# SCH1.net
KiCad netlist of a schematic drawn in Altium Designer
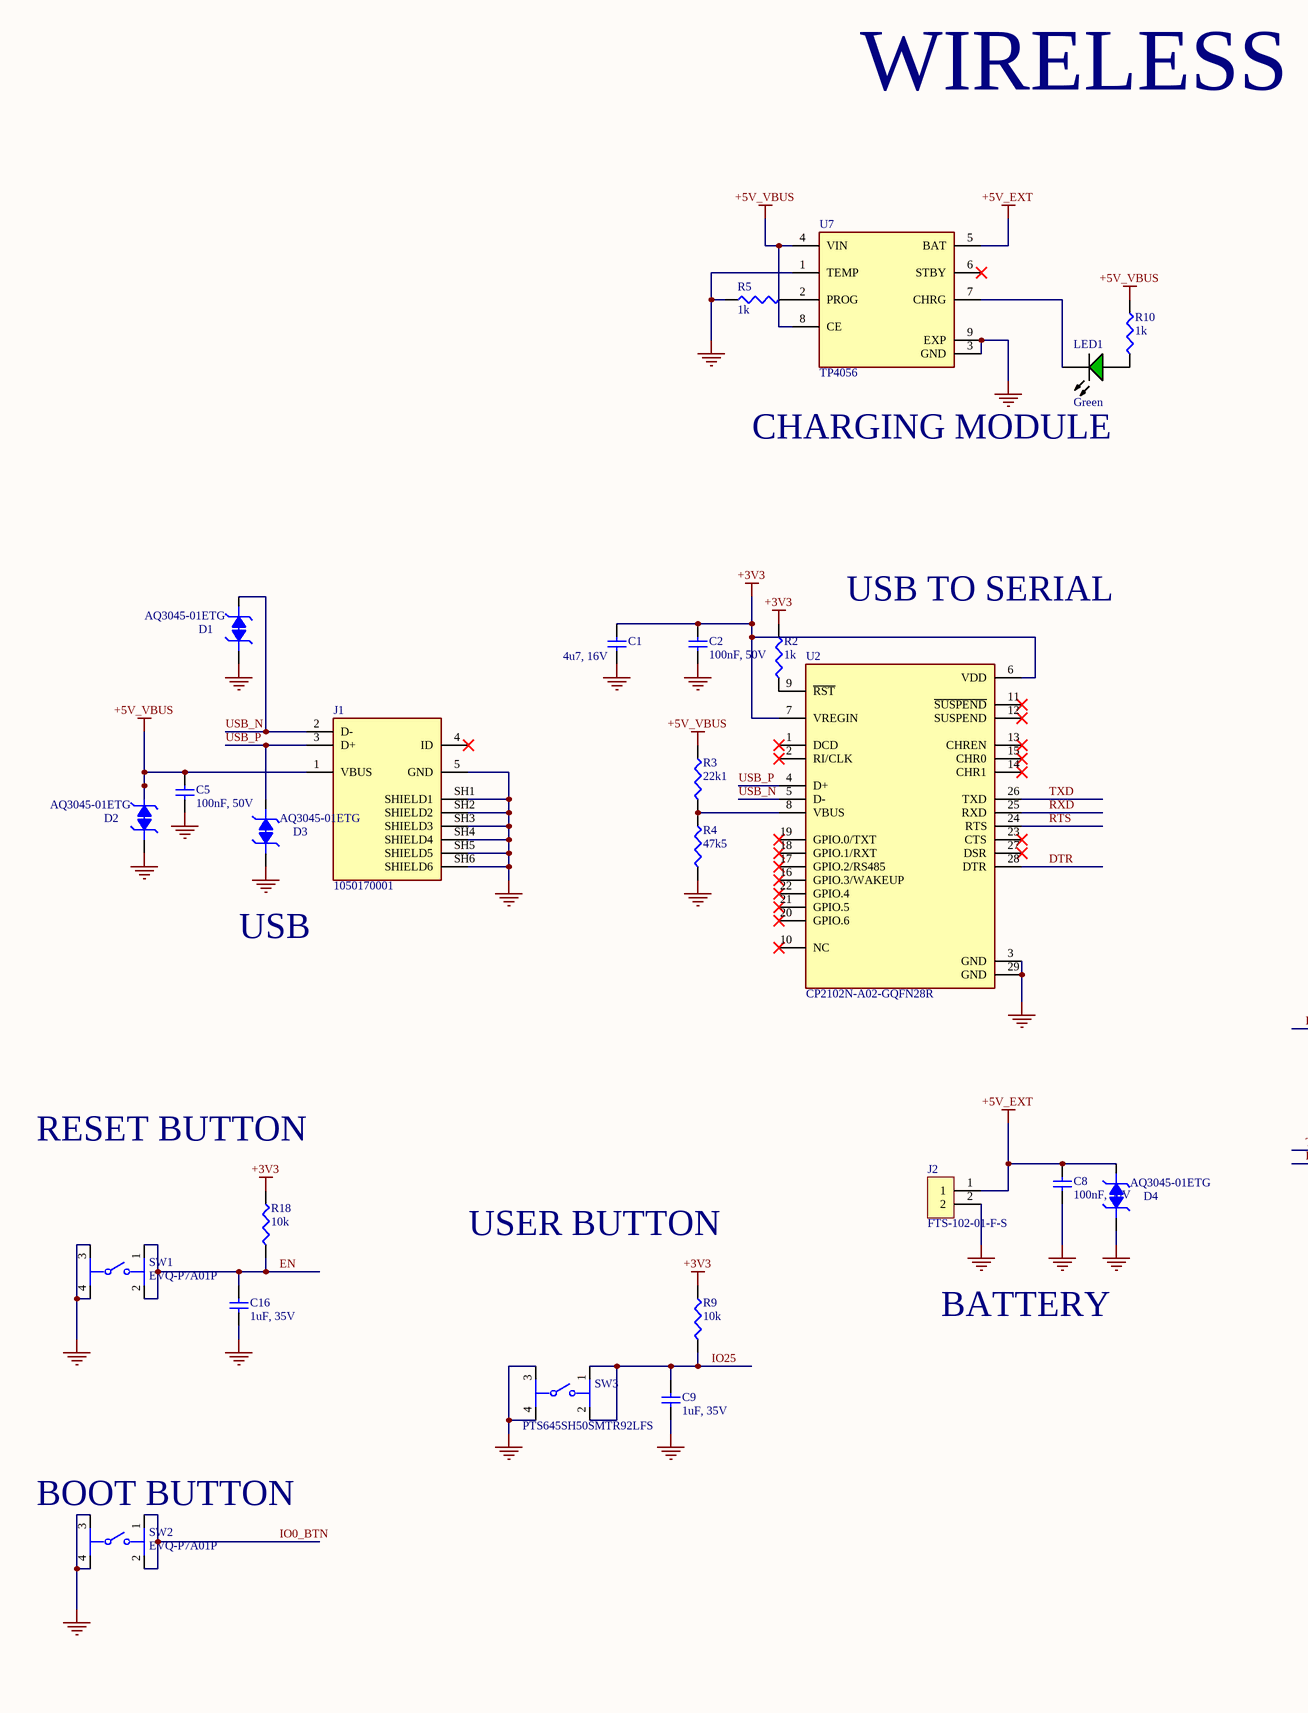
[diagram p0: SCH1.SchDoc, left]
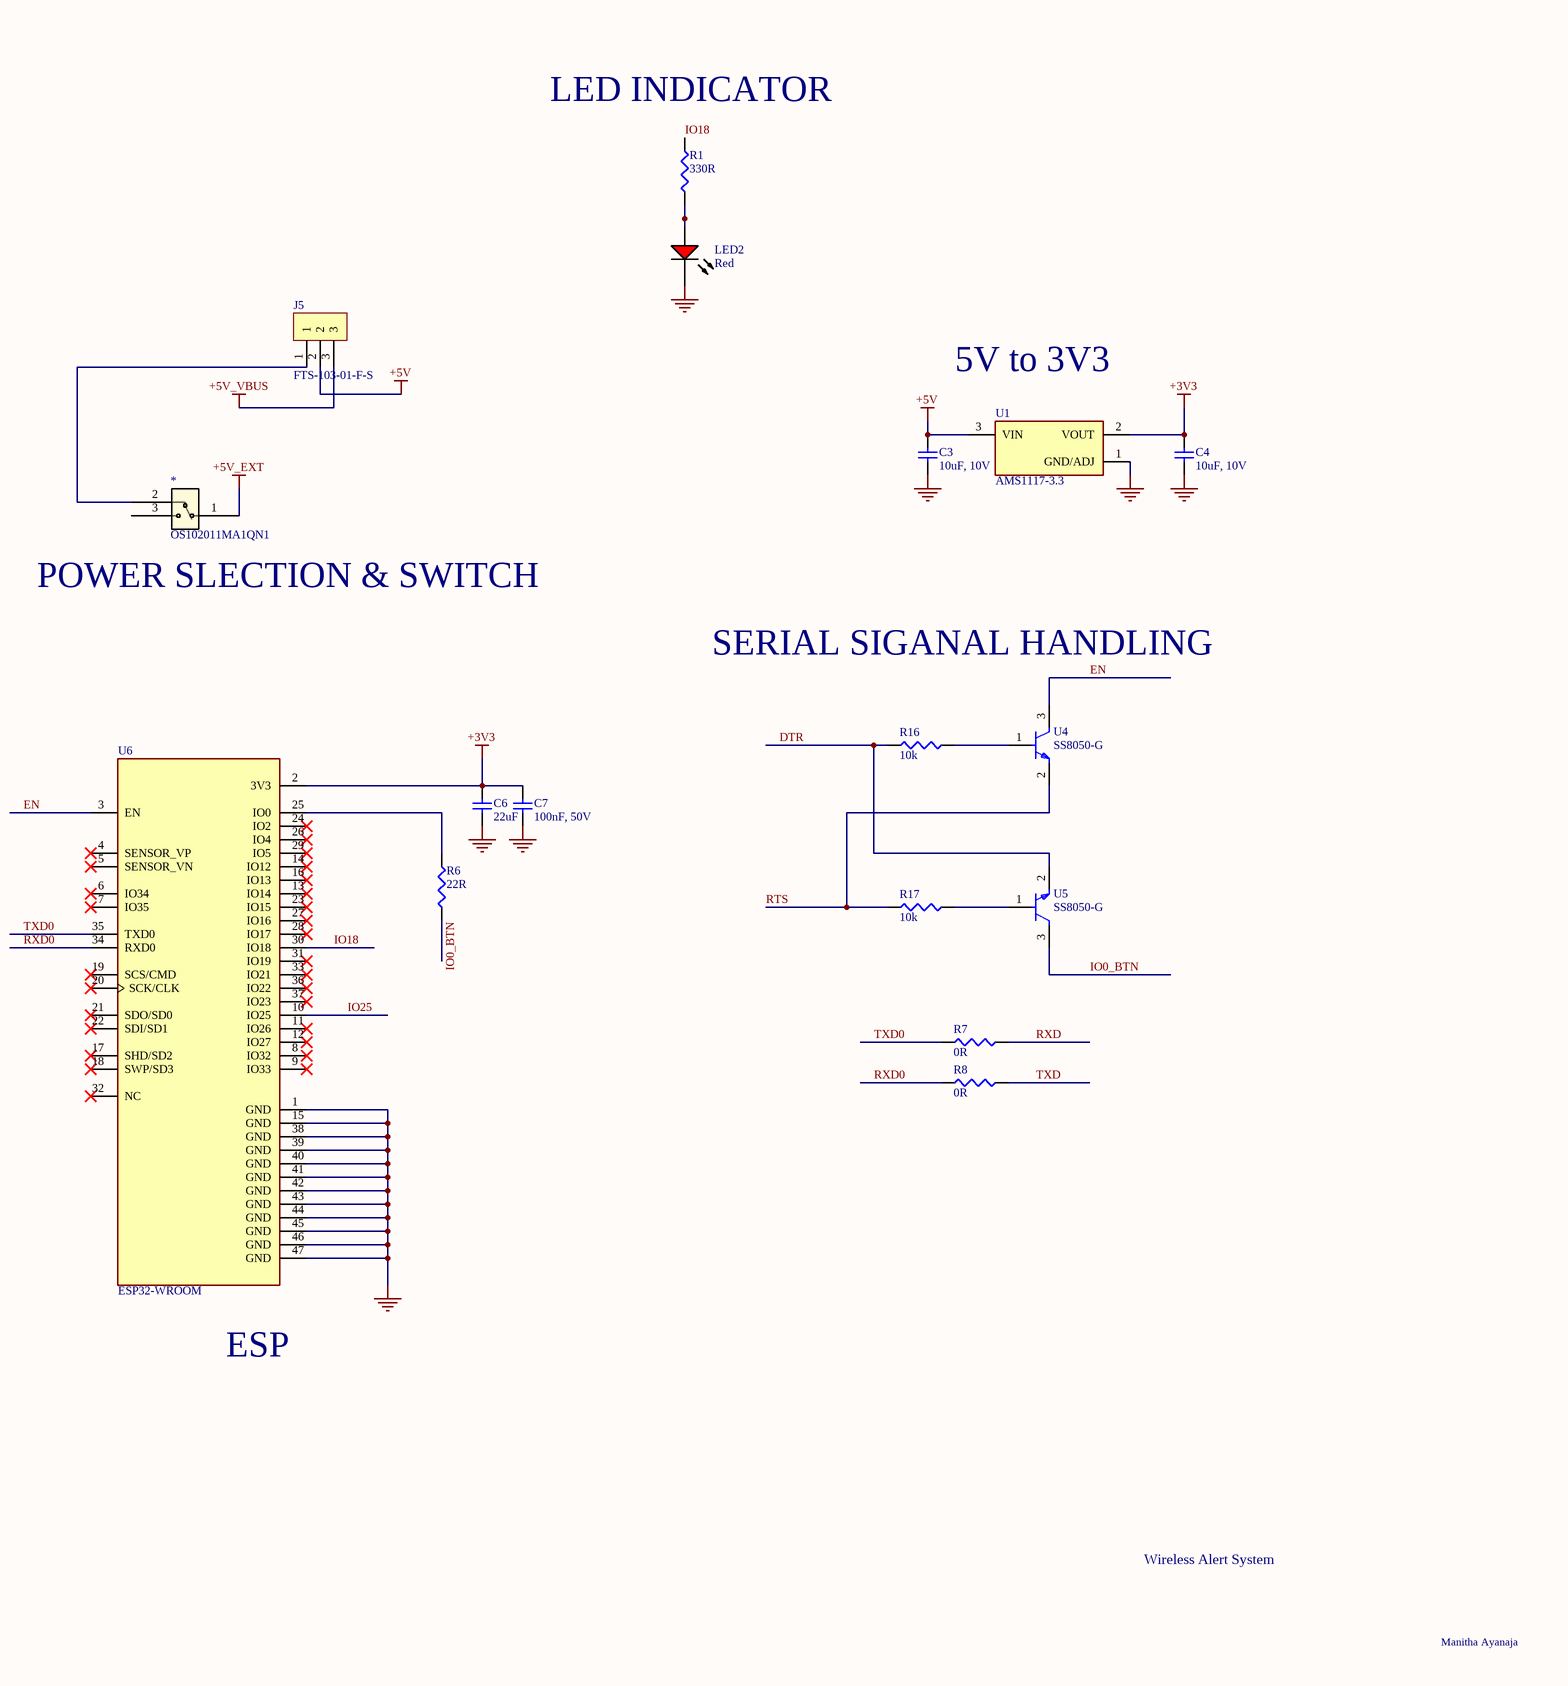
[diagram p1: SCH1.SchDoc, right]

(export (version "E")
  (design (tool "Eeschema 10.0.6"))
  (components
    (comp (ref "*")
      (value "OS102011MA1QN1")
      (footprint "OS102011MA1QN1_CNK")
      (description "Slide Switch, SPDT, Latched, 0.1A, 12VDC, Solder Terminal, Through Hole-right Angle")
      (fields (field (name "MANUFACTURER") "ITT C&K"))
      (libsource (lib "Schlib") (part "OS102011MA1QN1"))
    )
    (comp (ref "C1")
      (value "4u7, 16V")
      (footprint "CAPC1005X70N")
      (description "CAP CER 4.7UF 16V X5R 0402")
      (fields
        (field (name "MANUFACTURER") "Samsung")
        (field (name "MANUFACTURER PART NUMBER") "CL05A475MO5NUNC")
      )
      (libsource (lib "Schlib") (part "CL05A475MO5NUNC"))
    )
    (comp (ref "C2")
      (value "100nF, 50V")
      (footprint "CAPC1005X70N")
      (description "CAP CER 0.1UF 50V X7R 0402")
      (fields
        (field (name "MANUFACTURER") "Samsung")
        (field (name "MANUFACTURER PART NUMBER") "CL05B104KB54PNC")
      )
      (libsource (lib "Schlib") (part "CL05B104KB54PNC"))
    )
    (comp (ref "C3")
      (value "10uF, 10V")
      (footprint "CAPC1005X70N")
      (description "CAP CER 10UF 10V X5R 0402")
      (fields
        (field (name "MANUFACTURER") "Samsung")
        (field (name "MANUFACTURER PART NUMBER") "CL05A106MP8NUB8")
      )
      (libsource (lib "Schlib") (part "CL05A106MP8NUB8"))
    )
    (comp (ref "C4")
      (value "10uF, 10V")
      (footprint "CAPC1005X70N")
      (description "CAP CER 10UF 10V X5R 0402")
      (fields
        (field (name "MANUFACTURER") "Samsung")
        (field (name "MANUFACTURER PART NUMBER") "CL05A106MP8NUB8")
      )
      (libsource (lib "Schlib") (part "CL05A106MP8NUB8"))
    )
    (comp (ref "C5")
      (value "100nF, 50V")
      (footprint "CAPC1005X70N")
      (description "CAP CER 0.1UF 50V X7R 0402")
      (fields
        (field (name "MANUFACTURER") "Samsung")
        (field (name "MANUFACTURER PART NUMBER") "CL05B104KB54PNC")
      )
      (libsource (lib "Schlib") (part "CL05B104KB54PNC"))
    )
    (comp (ref "C6")
      (value "22uF")
      (footprint "CAPC1005X70N")
      (description "22 µF ±20% 6.3V Ceramic Capacitor X5R 0402 (1005 Metric)")
      (fields
        (field (name "MANUFACTURER") "Samsung")
        (field (name "MANUFACTURER PART NUMBER") "CL05A226MQ5QUNC")
      )
      (libsource (lib "Schlib") (part "CL05A226MQ5QUNC"))
    )
    (comp (ref "C7")
      (value "100nF, 50V")
      (footprint "CAPC1005X70N")
      (description "CAP CER 0.1UF 50V X7R 0402")
      (fields
        (field (name "MANUFACTURER") "Samsung")
        (field (name "MANUFACTURER PART NUMBER") "CL05B104KB54PNC")
      )
      (libsource (lib "Schlib") (part "CL05B104KB54PNC"))
    )
    (comp (ref "C8")
      (value "100nF, 50V")
      (footprint "CAPC1005X70N")
      (description "CAP CER 0.1UF 50V X7R 0402")
      (fields
        (field (name "MANUFACTURER") "Samsung")
        (field (name "MANUFACTURER PART NUMBER") "CL05B104KB54PNC")
      )
      (libsource (lib "Schlib") (part "CL05B104KB54PNC"))
    )
    (comp (ref "C9")
      (value "1uF, 35V")
      (footprint "CAPC1005X70N")
      (description "1 µF ±10% 35V Ceramic Capacitor X5R 0402 (1005 Metric)")
      (fields
        (field (name "MANUFACTURER") "Samsung")
        (field (name "MANUFACTURER PART NUMBER") "CL05A105KL5NRNC")
      )
      (libsource (lib "Schlib") (part "CL05A105KL5NRNC"))
    )
    (comp (ref "C16")
      (value "1uF, 35V")
      (footprint "CAPC1005X70N")
      (description "1 µF ±10% 35V Ceramic Capacitor X5R 0402 (1005 Metric)")
      (fields
        (field (name "MANUFACTURER") "Samsung")
        (field (name "MANUFACTURER PART NUMBER") "CL05A105KL5NRNC")
      )
      (libsource (lib "Schlib") (part "CL05A105KL5NRNC"))
    )
    (comp (ref "D1")
      (value "AQ3045-01ETG")
      (footprint "SOD882")
      (description "TVS DIODE 5.3VWM 12VC SOD882")
      (fields (field (name "MANUFACTURER") "Littelfuse") (field (name "LCSC PART NUMBER") "C3710326"))
      (libsource (lib "Schlib") (part "AQ3045-01ETG"))
    )
    (comp (ref "D2")
      (value "AQ3045-01ETG")
      (footprint "SOD882")
      (description "TVS DIODE 5.3VWM 12VC SOD882")
      (fields (field (name "MANUFACTURER") "Littelfuse") (field (name "LCSC PART NUMBER") "C3710326"))
      (libsource (lib "Schlib") (part "AQ3045-01ETG"))
    )
    (comp (ref "D3")
      (value "AQ3045-01ETG")
      (footprint "SOD882")
      (description "TVS DIODE 5.3VWM 12VC SOD882")
      (fields (field (name "MANUFACTURER") "Littelfuse") (field (name "LCSC PART NUMBER") "C3710326"))
      (libsource (lib "Schlib") (part "AQ3045-01ETG"))
    )
    (comp (ref "D4")
      (value "AQ3045-01ETG")
      (footprint "SOD882")
      (description "TVS DIODE 5.3VWM 12VC SOD882")
      (fields (field (name "MANUFACTURER") "Littelfuse") (field (name "LCSC PART NUMBER") "C3710326"))
      (libsource (lib "Schlib") (part "AQ3045-01ETG"))
    )
    (comp (ref "J1")
      (value "1050170001")
      (footprint "MOLEX_1050170001")
      (description "CONN RCPT USB2.0 MICRO B SMD R/A")
      (fields (field (name "MANUFACTURER") "Molex") (field (name "LCSC PART NUMBER") "C136000"))
      (libsource (lib "Schlib") (part "1050170001"))
    )
    (comp (ref "J2")
      (value "FTS-102-01-F-S")
      (footprint "HDR_1X2_1.27MM")
      (description "Connector Header Through Hole 2 position 0.050\" (1.27mm)")
      (fields (field (name "MANUFACTURER") "Samtec") (field (name "LCSC PART NUMBER") "C6045317"))
      (libsource (lib "Schlib") (part "FTS-102-01-F-S"))
    )
    (comp (ref "J5")
      (value "FTS-103-01-F-S")
      (footprint "HDR_1X3_1.27MM")
      (description "CONN HEADER VERT 3POS 1.27MM")
      (fields (field (name "MANUFACTURER") "Samtec") (field (name "LCSC PART NUMBER") "C3333578"))
      (libsource (lib "Schlib") (part "FTS-103-01-F-S"))
    )
    (comp (ref "LED1")
      (value "Green")
      (footprint "LEDC2012X120N")
      (description "Green LED Indication - Discrete 2V 0805 (2012 Metric)")
      (fields (field (name "LCSC PART NUMBER") "C6296788"))
      (libsource (lib "Schlib") (part "CMP-1724-00001-1"))
    )
    (comp (ref "LED2")
      (value "Red")
      (footprint "LEDC2012X120N")
      (description "Red LED Indication - Discrete 2V 0805 (2012 Metric)")
      (fields
        (field (name "MANUFACTURER") "Lumex")
        (field (name "MANUFACTURER PART NUMBER") "SML-LXT0805IW-TR")
      )
      (libsource (lib "Schlib") (part "SML-LXT0805IW-TR"))
    )
    (comp (ref "R1")
      (value "330R")
      (footprint "RESC1005X40N")
      (description "330 Ohms ±1% 0.063W, 1/16W Chip Resistor 0402 (1005 Metric) Moisture Resistant Thick Film")
      (fields
        (field (name "MANUFACTURER") "Yageo")
        (field (name "MANUFACTURER PART NUMBER") "RC0402FR-07330RL")
      )
      (libsource (lib "Schlib") (part "RC0402FR-07330RL"))
    )
    (comp (ref "R2")
      (value "1k")
      (footprint "RESC1005X40N")
      (description "1 kOhms ±1% 0.063W, 1/16W Chip Resistor 0402 (1005 Metric) Moisture Resistant Thick Film")
      (fields
        (field (name "MANUFACTURER") "Yageo")
        (field (name "MANUFACTURER PART NUMBER") "RC0402FR-071KL")
      )
      (libsource (lib "Schlib") (part "RC0402FR-071KL"))
    )
    (comp (ref "R3")
      (value "22k1")
      (footprint "RESC1005X40N")
      (description "22.1 kOhms ±1% 0.063W, 1/16W Chip Resistor 0402 (1005 Metric) Moisture Resistant Thick Film")
      (fields
        (field (name "MANUFACTURER") "Yageo")
        (field (name "MANUFACTURER PART NUMBER") "RC0402FR-0722K1L")
      )
      (libsource (lib "Schlib") (part "RC0402FR-0722K1L"))
    )
    (comp (ref "R4")
      (value "47k5")
      (footprint "RESC1005X40N")
      (description "47.5 kOhms ±1% 0.063W, 1/16W Chip Resistor 0402 (1005 Metric) Moisture Resistant Thick Film")
      (fields
        (field (name "MANUFACTURER") "Yageo")
        (field (name "MANUFACTURER PART NUMBER") "RC0402FR-1047K5L")
      )
      (libsource (lib "Schlib") (part "RC0402FR-1047K5L"))
    )
    (comp (ref "R5")
      (value "1k")
      (footprint "RESC1005X40N")
      (description "1 kOhms ±1% 0.063W, 1/16W Chip Resistor 0402 (1005 Metric) Moisture Resistant Thick Film")
      (fields
        (field (name "MANUFACTURER") "Yageo")
        (field (name "MANUFACTURER PART NUMBER") "RC0402FR-071KL")
      )
      (libsource (lib "Schlib") (part "RC0402FR-071KL"))
    )
    (comp (ref "R6")
      (value "22R")
      (footprint "RESC1005X40N")
      (description "RES 22 OHM 1% 1/16W 0402")
      (fields
        (field (name "MANUFACTURER") "Yageo")
        (field (name "MANUFACTURER PART NUMBER") "RC0402FR-0722RL")
      )
      (libsource (lib "Schlib") (part "RC0402FR-0722RL"))
    )
    (comp (ref "R7")
      (value "0R")
      (footprint "RESC1005X40N")
      (description "RES 0 OHM JUMPER 1/16W 0402")
      (fields
        (field (name "MANUFACTURER") "Yageo")
        (field (name "MANUFACTURER PART NUMBER") "RC0402JR-070RL")
      )
      (libsource (lib "Schlib") (part "RC0402JR-070RL"))
    )
    (comp (ref "R8")
      (value "0R")
      (footprint "RESC1005X40N")
      (description "RES 0 OHM JUMPER 1/16W 0402")
      (fields
        (field (name "MANUFACTURER") "Yageo")
        (field (name "MANUFACTURER PART NUMBER") "RC0402JR-070RL")
      )
      (libsource (lib "Schlib") (part "RC0402JR-070RL"))
    )
    (comp (ref "R9")
      (value "10k")
      (footprint "RESC1005X40N")
      (description "RES SMD 10K OHM 1% 1/16W 0402")
      (fields
        (field (name "MANUFACTURER") "Yageo")
        (field (name "MANUFACTURER PART NUMBER") "AC0402FR-0710KL")
      )
      (libsource (lib "Schlib") (part "AC0402FR-0710KL"))
    )
    (comp (ref "R10")
      (value "1k")
      (footprint "RESC1005X40N")
      (description "1 kOhms ±1% 0.063W, 1/16W Chip Resistor 0402 (1005 Metric) Moisture Resistant Thick Film")
      (fields
        (field (name "MANUFACTURER") "Yageo")
        (field (name "MANUFACTURER PART NUMBER") "RC0402FR-071KL")
      )
      (libsource (lib "Schlib") (part "RC0402FR-071KL"))
    )
    (comp (ref "R16")
      (value "10k")
      (footprint "RESC1005X40N")
      (description "RES SMD 10K OHM 1% 1/16W 0402")
      (fields
        (field (name "MANUFACTURER") "Yageo")
        (field (name "MANUFACTURER PART NUMBER") "AC0402FR-0710KL")
      )
      (libsource (lib "Schlib") (part "AC0402FR-0710KL"))
    )
    (comp (ref "R17")
      (value "10k")
      (footprint "RESC1005X40N")
      (description "RES SMD 10K OHM 1% 1/16W 0402")
      (fields
        (field (name "MANUFACTURER") "Yageo")
        (field (name "MANUFACTURER PART NUMBER") "AC0402FR-0710KL")
      )
      (libsource (lib "Schlib") (part "AC0402FR-0710KL"))
    )
    (comp (ref "R18")
      (value "10k")
      (footprint "RESC1005X40N")
      (description "RES SMD 10K OHM 1% 1/16W 0402")
      (fields
        (field (name "MANUFACTURER") "Yageo")
        (field (name "MANUFACTURER PART NUMBER") "AC0402FR-0710KL")
      )
      (libsource (lib "Schlib") (part "AC0402FR-0710KL"))
    )
    (comp (ref "SW1")
      (value "EVQ-P7A01P")
      (footprint "SW_EVQ-P7A01P")
      (description "Tactile Switch SPST-NO Side Actuated Surface Mount, Right Angle")
      (fields (field (name "MANUFACTURER") "Panasonic") (field (name "LCSC PART NUMBER") "C79167"))
      (libsource (lib "Schlib") (part "EVQ-P7A01P"))
    )
    (comp (ref "SW2")
      (value "EVQ-P7A01P")
      (footprint "SW_EVQ-P7A01P")
      (description "Tactile Switch SPST-NO Side Actuated Surface Mount, Right Angle")
      (fields (field (name "MANUFACTURER") "Panasonic") (field (name "LCSC PART NUMBER") "C79167"))
      (libsource (lib "Schlib") (part "EVQ-P7A01P"))
    )
    (comp (ref "SW3")
      (value "PTS645SH50SMTR92LFS")
      (footprint "FP-PTS645SH50SMTR92LFS-MFG")
      (description "SWITCH TACTILE SPST-NO 0.05A 12V")
      (fields (field (name "MANUFACTURER") "ITT C&K") (field (name "LCSC PART NUMBER") "C221869"))
      (libsource (lib "Schlib") (part "PTS645SH50SMTR92LFS"))
    )
    (comp (ref "U1")
      (value "AMS1117-3.3")
      (footprint "AMS1117-3.3")
      (description "Linear Voltage Regulator IC Positive Fixed 1 Output 1A SOT-223-3L")
      (fields
        (field (name "MANUFACTURER") "UMW(Youtai Semiconductor Co., Ltd.)")
        (field (name "LCSC PART NUMBER") "C347222")
      )
      (libsource (lib "Schlib") (part "AMS1117-3.3"))
    )
    (comp (ref "U2")
      (value "CP2102N-A02-GQFN28R")
      (footprint "QFN50P500X500X80-29N")
      (description "USB Bridge, USB to UART USB 2.0 UART Interface 28-QFN (5x5)")
      (fields (field (name "MANUFACTURER") "Silicon Labs") (field (name "LCSC PART NUMBER") "C964632"))
      (libsource (lib "Schlib") (part "CP2102N-A02-GQFN28R"))
    )
    (comp (ref "U4")
      (value "SS8050-G")
      (footprint "FP-SS8050-G-IPC_B")
      (description "TRANS NPN 25V 1.5A SOT-23-3")
      (fields (field (name "MANUFACTURER") "Comchip") (field (name "LCSC PART NUMBER") "C164885"))
      (libsource (lib "Schlib") (part "SS8050-G"))
    )
    (comp (ref "U5")
      (value "SS8050-G")
      (footprint "FP-SS8050-G-IPC_B")
      (description "TRANS NPN 25V 1.5A SOT-23-3")
      (fields (field (name "MANUFACTURER") "Comchip") (field (name "LCSC PART NUMBER") "C164885"))
      (libsource (lib "Schlib") (part "SS8050-G"))
    )
    (comp (ref "U6")
      (value "ESP32-WROOM")
      (footprint "MODULE_ESP32-WROOM-32D-N4")
      (fields
        (field (name "MANUFACTURER") "Espressif Systems")
        (field (name "MANUFACTURER PART NUMBER") "ESP32-WROOM-32D-N4")
        (field (name "LCSC PART NUMBER") "C473012")
      )
      (libsource (lib "Schlib") (part "ESP32-WROOM-32D-N4"))
    )
    (comp (ref "U7")
      (value "TP4056")
      (footprint "SOIC127P600X170-9N")
      (description "LINEAR BATTERY CHARGER 1 CELL 8-")
      (fields
        (field (name "MANUFACTURER") "3PEAK")
        (field (name "MANUFACTURER PART NUMBER") "TPB4056B2X-ES1R")
      )
      (libsource (lib "Schlib") (part "TPB4056B2X-ES1R"))
    )
  )
  (nets
    (net (code "1") (name "+3V3") (class "Default")
      (node (ref "C1") (pin "2") (pintype "passive"))
      (node (ref "C2") (pin "2") (pintype "passive"))
      (node (ref "C4") (pin "2") (pintype "passive"))
      (node (ref "C6") (pin "2") (pintype "passive"))
      (node (ref "C7") (pin "2") (pintype "passive"))
      (node (ref "R18") (pin "2") (pinfunction "2_2") (pintype "passive"))
      (node (ref "R2") (pin "2") (pinfunction "2_2") (pintype "passive"))
      (node (ref "R9") (pin "2") (pinfunction "2_2") (pintype "passive"))
      (node (ref "U1") (pin "2") (pinfunction "VOUT_2") (pintype "passive"))
      (node (ref "U2") (pin "6") (pinfunction "VDD_6") (pintype "passive"))
      (node (ref "U2") (pin "7") (pinfunction "VREGIN_7") (pintype "passive"))
      (node (ref "U6") (pin "2") (pinfunction "3V3_2") (pintype "passive"))
    )
    (net (code "2") (name "+5V") (class "Default")
      (node (ref "C3") (pin "2") (pintype "passive"))
      (node (ref "J5") (pin "2") (pinfunction "2_2") (pintype "passive"))
      (node (ref "U1") (pin "3") (pinfunction "VIN_3") (pintype "passive"))
    )
    (net (code "3") (name "+5V_EXT") (class "Default")
      (node (ref "*") (pin "1") (pinfunction "1_1") (pintype "passive"))
      (node (ref "C8") (pin "2") (pintype "passive"))
      (node (ref "D4") (pin "2") (pinfunction "2_2") (pintype "passive"))
      (node (ref "J2") (pin "1") (pinfunction "1_1") (pintype "passive"))
      (node (ref "U7") (pin "5") (pinfunction "BAT_5") (pintype "passive"))
    )
    (net (code "4") (name "+5V_VBUS") (class "Default")
      (node (ref "C5") (pin "2") (pintype "passive"))
      (node (ref "D2") (pin "2") (pinfunction "2_2") (pintype "passive"))
      (node (ref "J1") (pin "1") (pinfunction "VBUS_1") (pintype "passive"))
      (node (ref "J5") (pin "3") (pinfunction "3_3") (pintype "passive"))
      (node (ref "R10") (pin "2") (pinfunction "2_2") (pintype "passive"))
      (node (ref "R3") (pin "2") (pinfunction "2_2") (pintype "passive"))
      (node (ref "U7") (pin "4") (pinfunction "VIN_4") (pintype "passive"))
      (node (ref "U7") (pin "8") (pinfunction "CE_8") (pintype "passive"))
    )
    (net (code "5") (name "/DTR") (class "Default")
      (node (ref "R16") (pin "2") (pinfunction "2_2") (pintype "passive"))
      (node (ref "U2") (pin "28") (pinfunction "DTR_28") (pintype "passive"))
      (node (ref "U5") (pin "2") (pinfunction "E_2") (pintype "passive"))
    )
    (net (code "6") (name "/EN") (class "Default")
      (node (ref "C16") (pin "2") (pintype "passive"))
      (node (ref "R18") (pin "1") (pinfunction "1_1") (pintype "passive"))
      (node (ref "SW1") (pin "1") (pinfunction "1_1") (pintype "passive"))
      (node (ref "SW1") (pin "2") (pinfunction "2_2") (pintype "passive"))
      (node (ref "U4") (pin "3") (pinfunction "C_3") (pintype "passive"))
      (node (ref "U6") (pin "3") (pinfunction "EN_3") (pintype "passive"))
    )
    (net (code "7") (name "/IO0_BTN") (class "Default")
      (node (ref "R6") (pin "1") (pinfunction "1_1") (pintype "passive"))
      (node (ref "SW2") (pin "1") (pinfunction "1_1") (pintype "passive"))
      (node (ref "SW2") (pin "2") (pinfunction "2_2") (pintype "passive"))
      (node (ref "U5") (pin "3") (pinfunction "C_3") (pintype "passive"))
    )
    (net (code "8") (name "/IO18") (class "Default")
      (node (ref "R1") (pin "2") (pinfunction "2_2") (pintype "passive"))
      (node (ref "U6") (pin "30") (pinfunction "IO18_30") (pintype "passive"))
    )
    (net (code "9") (name "/IO25") (class "Default")
      (node (ref "C9") (pin "2") (pintype "passive"))
      (node (ref "R9") (pin "1") (pinfunction "1_1") (pintype "passive"))
      (node (ref "SW3") (pin "1") (pinfunction "1_1") (pintype "passive"))
      (node (ref "SW3") (pin "2") (pinfunction "2_2") (pintype "passive"))
      (node (ref "U6") (pin "10") (pinfunction "IO25_10") (pintype "passive"))
    )
    (net (code "10") (name "/RTS") (class "Default")
      (node (ref "R17") (pin "2") (pinfunction "2_2") (pintype "passive"))
      (node (ref "U2") (pin "24") (pinfunction "RTS_24") (pintype "passive"))
      (node (ref "U4") (pin "2") (pinfunction "E_2") (pintype "passive"))
    )
    (net (code "11") (name "/RXD") (class "Default")
      (node (ref "R7") (pin "2") (pinfunction "2_2") (pintype "passive"))
      (node (ref "U2") (pin "25") (pinfunction "RXD_25") (pintype "passive"))
    )
    (net (code "12") (name "/RXD0") (class "Default")
      (node (ref "R8") (pin "1") (pinfunction "1_1") (pintype "passive"))
      (node (ref "U6") (pin "34") (pinfunction "RXD0_34") (pintype "passive"))
    )
    (net (code "13") (name "/TXD") (class "Default")
      (node (ref "R8") (pin "2") (pinfunction "2_2") (pintype "passive"))
      (node (ref "U2") (pin "26") (pinfunction "TXD_26") (pintype "passive"))
    )
    (net (code "14") (name "/TXD0") (class "Default")
      (node (ref "R7") (pin "1") (pinfunction "1_1") (pintype "passive"))
      (node (ref "U6") (pin "35") (pinfunction "TXD0_35") (pintype "passive"))
    )
    (net (code "15") (name "/USB_N") (class "Default")
      (node (ref "D1") (pin "2") (pinfunction "2_2") (pintype "passive"))
      (node (ref "J1") (pin "2") (pinfunction "D-_2") (pintype "passive"))
      (node (ref "U2") (pin "5") (pinfunction "D-_5") (pintype "passive"))
    )
    (net (code "16") (name "/USB_P") (class "Default")
      (node (ref "D3") (pin "2") (pinfunction "2_2") (pintype "passive"))
      (node (ref "J1") (pin "3") (pinfunction "D+_3") (pintype "passive"))
      (node (ref "U2") (pin "4") (pinfunction "D+_4") (pintype "passive"))
    )
    (net (code "17") (name "GND") (class "Default")
      (node (ref "C1") (pin "1") (pintype "passive"))
      (node (ref "C16") (pin "1") (pintype "passive"))
      (node (ref "C2") (pin "1") (pintype "passive"))
      (node (ref "C3") (pin "1") (pintype "passive"))
      (node (ref "C4") (pin "1") (pintype "passive"))
      (node (ref "C5") (pin "1") (pintype "passive"))
      (node (ref "C6") (pin "1") (pintype "passive"))
      (node (ref "C7") (pin "1") (pintype "passive"))
      (node (ref "C8") (pin "1") (pintype "passive"))
      (node (ref "C9") (pin "1") (pintype "passive"))
      (node (ref "D1") (pin "1") (pinfunction "1_1") (pintype "passive"))
      (node (ref "D2") (pin "1") (pinfunction "1_1") (pintype "passive"))
      (node (ref "D3") (pin "1") (pinfunction "1_1") (pintype "passive"))
      (node (ref "D4") (pin "1") (pinfunction "1_1") (pintype "passive"))
      (node (ref "J1") (pin "5") (pinfunction "GND_5") (pintype "passive"))
      (node (ref "J1") (pin "SH1") (pinfunction "SHIELD1_SH1") (pintype "passive"))
      (node (ref "J1") (pin "SH2") (pinfunction "SHIELD2_SH2") (pintype "passive"))
      (node (ref "J1") (pin "SH3") (pinfunction "SHIELD3_SH3") (pintype "passive"))
      (node (ref "J1") (pin "SH4") (pinfunction "SHIELD4_SH4") (pintype "passive"))
      (node (ref "J1") (pin "SH5") (pinfunction "SHIELD5_SH5") (pintype "passive"))
      (node (ref "J1") (pin "SH6") (pinfunction "SHIELD6_SH6") (pintype "passive"))
      (node (ref "J2") (pin "2") (pinfunction "2_2") (pintype "passive"))
      (node (ref "LED2") (pin "2") (pinfunction "K_2") (pintype "passive"))
      (node (ref "R4") (pin "1") (pinfunction "1_1") (pintype "passive"))
      (node (ref "R5") (pin "1") (pinfunction "1_1") (pintype "passive"))
      (node (ref "SW1") (pin "3") (pinfunction "3_3") (pintype "passive"))
      (node (ref "SW1") (pin "4") (pinfunction "4_4") (pintype "passive"))
      (node (ref "SW2") (pin "3") (pinfunction "3_3") (pintype "passive"))
      (node (ref "SW2") (pin "4") (pinfunction "4_4") (pintype "passive"))
      (node (ref "SW3") (pin "3") (pinfunction "3_3") (pintype "passive"))
      (node (ref "SW3") (pin "4") (pinfunction "4_4") (pintype "passive"))
      (node (ref "U1") (pin "1") (pinfunction "GND/ADJ_1") (pintype "passive"))
      (node (ref "U2") (pin "29") (pinfunction "GND_29") (pintype "passive"))
      (node (ref "U2") (pin "3") (pinfunction "GND_3") (pintype "passive"))
      (node (ref "U6") (pin "1") (pinfunction "GND_1") (pintype "passive"))
      (node (ref "U6") (pin "15") (pinfunction "GND_15") (pintype "passive"))
      (node (ref "U6") (pin "38") (pinfunction "GND_38") (pintype "passive"))
      (node (ref "U6") (pin "39") (pinfunction "GND_39") (pintype "passive"))
      (node (ref "U6") (pin "40") (pinfunction "GND_40") (pintype "passive"))
      (node (ref "U6") (pin "41") (pinfunction "GND_41") (pintype "passive"))
      (node (ref "U6") (pin "42") (pinfunction "GND_42") (pintype "passive"))
      (node (ref "U6") (pin "43") (pinfunction "GND_43") (pintype "passive"))
      (node (ref "U6") (pin "44") (pinfunction "GND_44") (pintype "passive"))
      (node (ref "U6") (pin "45") (pinfunction "GND_45") (pintype "passive"))
      (node (ref "U6") (pin "46") (pinfunction "GND_46") (pintype "passive"))
      (node (ref "U6") (pin "47") (pinfunction "GND_47") (pintype "passive"))
      (node (ref "U7") (pin "1") (pinfunction "TEMP_1") (pintype "passive"))
      (node (ref "U7") (pin "3") (pinfunction "GND_3") (pintype "passive"))
      (node (ref "U7") (pin "9") (pinfunction "EXP_9") (pintype "passive"))
    )
    (net (code "18") (name "Net-(*-Pad2)") (class "Default")
      (node (ref "*") (pin "2") (pinfunction "2_2") (pintype "passive"))
      (node (ref "J5") (pin "1") (pinfunction "1_1") (pintype "passive"))
    )
    (net (code "19") (name "Net-(LED1-A)") (class "Default")
      (node (ref "LED1") (pin "1") (pinfunction "A_1") (pintype "passive"))
      (node (ref "R10") (pin "1") (pinfunction "1_1") (pintype "passive"))
    )
    (net (code "20") (name "Net-(LED1-K)") (class "Default")
      (node (ref "LED1") (pin "2") (pinfunction "K_2") (pintype "passive"))
      (node (ref "U7") (pin "7") (pinfunction "CHRG_7") (pintype "passive"))
    )
    (net (code "21") (name "Net-(LED2-A)") (class "Default")
      (node (ref "LED2") (pin "1") (pinfunction "A_1") (pintype "passive"))
      (node (ref "R1") (pin "1") (pinfunction "1_1") (pintype "passive"))
    )
    (net (code "22") (name "Net-(U2-VBUS)") (class "Default")
      (node (ref "R3") (pin "1") (pinfunction "1_1") (pintype "passive"))
      (node (ref "R4") (pin "2") (pinfunction "2_2") (pintype "passive"))
      (node (ref "U2") (pin "8") (pinfunction "VBUS_8") (pintype "passive"))
    )
    (net (code "23") (name "Net-(U2-~{RST})") (class "Default")
      (node (ref "R2") (pin "1") (pinfunction "1_1") (pintype "passive"))
      (node (ref "U2") (pin "9") (pinfunction "~{RST}_9") (pintype "passive"))
    )
    (net (code "24") (name "Net-(U4-B)") (class "Default")
      (node (ref "R16") (pin "1") (pinfunction "1_1") (pintype "passive"))
      (node (ref "U4") (pin "1") (pinfunction "B_1") (pintype "passive"))
    )
    (net (code "25") (name "Net-(U5-B)") (class "Default")
      (node (ref "R17") (pin "1") (pinfunction "1_1") (pintype "passive"))
      (node (ref "U5") (pin "1") (pinfunction "B_1") (pintype "passive"))
    )
    (net (code "26") (name "Net-(U6-IO0)") (class "Default")
      (node (ref "R6") (pin "2") (pinfunction "2_2") (pintype "passive"))
      (node (ref "U6") (pin "25") (pinfunction "IO0_25") (pintype "passive"))
    )
    (net (code "27") (name "Net-(U7-PROG)") (class "Default")
      (node (ref "R5") (pin "2") (pinfunction "2_2") (pintype "passive"))
      (node (ref "U7") (pin "2") (pinfunction "PROG_2") (pintype "passive"))
    )
    (net (code "28") (name "unconnected-(*-Pad3)") (class "Default")
      (node (ref "*") (pin "3") (pinfunction "3_3") (pintype "passive"))
    )
    (net (code "29") (name "unconnected-(J1-ID-Pad4)") (class "Default")
      (node (ref "J1") (pin "4") (pinfunction "ID_4") (pintype "passive+no_connect"))
    )
    (net (code "30") (name "unconnected-(U2-CHR0-Pad15)") (class "Default")
      (node (ref "U2") (pin "15") (pinfunction "CHR0_15") (pintype "passive+no_connect"))
    )
    (net (code "31") (name "unconnected-(U2-CHR1-Pad14)") (class "Default")
      (node (ref "U2") (pin "14") (pinfunction "CHR1_14") (pintype "passive+no_connect"))
    )
    (net (code "32") (name "unconnected-(U2-CHREN-Pad13)") (class "Default")
      (node (ref "U2") (pin "13") (pinfunction "CHREN_13") (pintype "passive+no_connect"))
    )
    (net (code "33") (name "unconnected-(U2-CTS-Pad23)") (class "Default")
      (node (ref "U2") (pin "23") (pinfunction "CTS_23") (pintype "passive+no_connect"))
    )
    (net (code "34") (name "unconnected-(U2-DCD-Pad1)") (class "Default")
      (node (ref "U2") (pin "1") (pinfunction "DCD_1") (pintype "passive+no_connect"))
    )
    (net (code "35") (name "unconnected-(U2-DSR-Pad27)") (class "Default")
      (node (ref "U2") (pin "27") (pinfunction "DSR_27") (pintype "passive+no_connect"))
    )
    (net (code "36") (name "unconnected-(U2-GPIO.0{slash}TXT-Pad19)") (class "Default")
      (node (ref "U2") (pin "19") (pinfunction "GPIO.0/TXT_19") (pintype "passive+no_connect"))
    )
    (net (code "37") (name "unconnected-(U2-GPIO.1{slash}RXT-Pad18)") (class "Default")
      (node (ref "U2") (pin "18") (pinfunction "GPIO.1/RXT_18") (pintype "passive+no_connect"))
    )
    (net (code "38") (name "unconnected-(U2-GPIO.2{slash}RS485-Pad17)") (class "Default")
      (node (ref "U2") (pin "17") (pinfunction "GPIO.2/RS485_17") (pintype "passive+no_connect"))
    )
    (net (code "39") (name "unconnected-(U2-GPIO.3{slash}WAKEUP-Pad16)") (class "Default")
      (node (ref "U2") (pin "16") (pinfunction "GPIO.3/WAKEUP_16") (pintype "passive+no_connect"))
    )
    (net (code "40") (name "unconnected-(U2-GPIO.4-Pad22)") (class "Default")
      (node (ref "U2") (pin "22") (pinfunction "GPIO.4_22") (pintype "passive+no_connect"))
    )
    (net (code "41") (name "unconnected-(U2-GPIO.5-Pad21)") (class "Default")
      (node (ref "U2") (pin "21") (pinfunction "GPIO.5_21") (pintype "passive+no_connect"))
    )
    (net (code "42") (name "unconnected-(U2-GPIO.6-Pad20)") (class "Default")
      (node (ref "U2") (pin "20") (pinfunction "GPIO.6_20") (pintype "passive+no_connect"))
    )
    (net (code "43") (name "unconnected-(U2-NC-Pad10)") (class "Default")
      (node (ref "U2") (pin "10") (pinfunction "NC_10") (pintype "passive+no_connect"))
    )
    (net (code "44") (name "unconnected-(U2-RI{slash}CLK-Pad2)") (class "Default")
      (node (ref "U2") (pin "2") (pinfunction "RI/CLK_2") (pintype "passive+no_connect"))
    )
    (net (code "45") (name "unconnected-(U2-SUSPEND-Pad12)") (class "Default")
      (node (ref "U2") (pin "12") (pinfunction "SUSPEND_12") (pintype "passive+no_connect"))
    )
    (net (code "46") (name "unconnected-(U2-~{SUSPEND}-Pad11)") (class "Default")
      (node (ref "U2") (pin "11") (pinfunction "~{SUSPEND}_11") (pintype "passive+no_connect"))
    )
    (net (code "47") (name "unconnected-(U6-IO2-Pad24)") (class "Default")
      (node (ref "U6") (pin "24") (pinfunction "IO2_24") (pintype "passive+no_connect"))
    )
    (net (code "48") (name "unconnected-(U6-IO4-Pad26)") (class "Default")
      (node (ref "U6") (pin "26") (pinfunction "IO4_26") (pintype "passive+no_connect"))
    )
    (net (code "49") (name "unconnected-(U6-IO5-Pad29)") (class "Default")
      (node (ref "U6") (pin "29") (pinfunction "IO5_29") (pintype "passive+no_connect"))
    )
    (net (code "50") (name "unconnected-(U6-IO12-Pad14)") (class "Default")
      (node (ref "U6") (pin "14") (pinfunction "IO12_14") (pintype "passive+no_connect"))
    )
    (net (code "51") (name "unconnected-(U6-IO13-Pad16)") (class "Default")
      (node (ref "U6") (pin "16") (pinfunction "IO13_16") (pintype "passive+no_connect"))
    )
    (net (code "52") (name "unconnected-(U6-IO14-Pad13)") (class "Default")
      (node (ref "U6") (pin "13") (pinfunction "IO14_13") (pintype "passive+no_connect"))
    )
    (net (code "53") (name "unconnected-(U6-IO15-Pad23)") (class "Default")
      (node (ref "U6") (pin "23") (pinfunction "IO15_23") (pintype "passive+no_connect"))
    )
    (net (code "54") (name "unconnected-(U6-IO16-Pad27)") (class "Default")
      (node (ref "U6") (pin "27") (pinfunction "IO16_27") (pintype "passive+no_connect"))
    )
    (net (code "55") (name "unconnected-(U6-IO17-Pad28)") (class "Default")
      (node (ref "U6") (pin "28") (pinfunction "IO17_28") (pintype "passive+no_connect"))
    )
    (net (code "56") (name "unconnected-(U6-IO19-Pad31)") (class "Default")
      (node (ref "U6") (pin "31") (pinfunction "IO19_31") (pintype "passive+no_connect"))
    )
    (net (code "57") (name "unconnected-(U6-IO21-Pad33)") (class "Default")
      (node (ref "U6") (pin "33") (pinfunction "IO21_33") (pintype "passive+no_connect"))
    )
    (net (code "58") (name "unconnected-(U6-IO22-Pad36)") (class "Default")
      (node (ref "U6") (pin "36") (pinfunction "IO22_36") (pintype "passive+no_connect"))
    )
    (net (code "59") (name "unconnected-(U6-IO23-Pad37)") (class "Default")
      (node (ref "U6") (pin "37") (pinfunction "IO23_37") (pintype "passive+no_connect"))
    )
    (net (code "60") (name "unconnected-(U6-IO26-Pad11)") (class "Default")
      (node (ref "U6") (pin "11") (pinfunction "IO26_11") (pintype "passive+no_connect"))
    )
    (net (code "61") (name "unconnected-(U6-IO27-Pad12)") (class "Default")
      (node (ref "U6") (pin "12") (pinfunction "IO27_12") (pintype "passive+no_connect"))
    )
    (net (code "62") (name "unconnected-(U6-IO32-Pad8)") (class "Default")
      (node (ref "U6") (pin "8") (pinfunction "IO32_8") (pintype "passive+no_connect"))
    )
    (net (code "63") (name "unconnected-(U6-IO33-Pad9)") (class "Default")
      (node (ref "U6") (pin "9") (pinfunction "IO33_9") (pintype "passive+no_connect"))
    )
    (net (code "64") (name "unconnected-(U6-IO34-Pad6)") (class "Default")
      (node (ref "U6") (pin "6") (pinfunction "IO34_6") (pintype "passive+no_connect"))
    )
    (net (code "65") (name "unconnected-(U6-IO35-Pad7)") (class "Default")
      (node (ref "U6") (pin "7") (pinfunction "IO35_7") (pintype "passive+no_connect"))
    )
    (net (code "66") (name "unconnected-(U6-NC-Pad32)") (class "Default")
      (node (ref "U6") (pin "32") (pinfunction "NC_32") (pintype "passive+no_connect"))
    )
    (net (code "67") (name "unconnected-(U6-SCK{slash}CLK-Pad20)") (class "Default")
      (node (ref "U6") (pin "20") (pinfunction "SCK/CLK_20") (pintype "passive+no_connect"))
    )
    (net (code "68") (name "unconnected-(U6-SCS{slash}CMD-Pad19)") (class "Default")
      (node (ref "U6") (pin "19") (pinfunction "SCS/CMD_19") (pintype "passive+no_connect"))
    )
    (net (code "69") (name "unconnected-(U6-SDI{slash}SD1-Pad22)") (class "Default")
      (node (ref "U6") (pin "22") (pinfunction "SDI/SD1_22") (pintype "passive+no_connect"))
    )
    (net (code "70") (name "unconnected-(U6-SDO{slash}SD0-Pad21)") (class "Default")
      (node (ref "U6") (pin "21") (pinfunction "SDO/SD0_21") (pintype "passive+no_connect"))
    )
    (net (code "71") (name "unconnected-(U6-SENSOR_VN-Pad5)") (class "Default")
      (node (ref "U6") (pin "5") (pinfunction "SENSOR_VN_5") (pintype "passive+no_connect"))
    )
    (net (code "72") (name "unconnected-(U6-SENSOR_VP-Pad4)") (class "Default")
      (node (ref "U6") (pin "4") (pinfunction "SENSOR_VP_4") (pintype "passive+no_connect"))
    )
    (net (code "73") (name "unconnected-(U6-SHD{slash}SD2-Pad17)") (class "Default")
      (node (ref "U6") (pin "17") (pinfunction "SHD/SD2_17") (pintype "passive+no_connect"))
    )
    (net (code "74") (name "unconnected-(U6-SWP{slash}SD3-Pad18)") (class "Default")
      (node (ref "U6") (pin "18") (pinfunction "SWP/SD3_18") (pintype "passive+no_connect"))
    )
    (net (code "75") (name "unconnected-(U7-STBY-Pad6)") (class "Default")
      (node (ref "U7") (pin "6") (pinfunction "STBY_6") (pintype "passive+no_connect"))
    )
  )
)
